# 08_DRIVER.net
KiCad netlist of a schematic drawn in Altium Designer
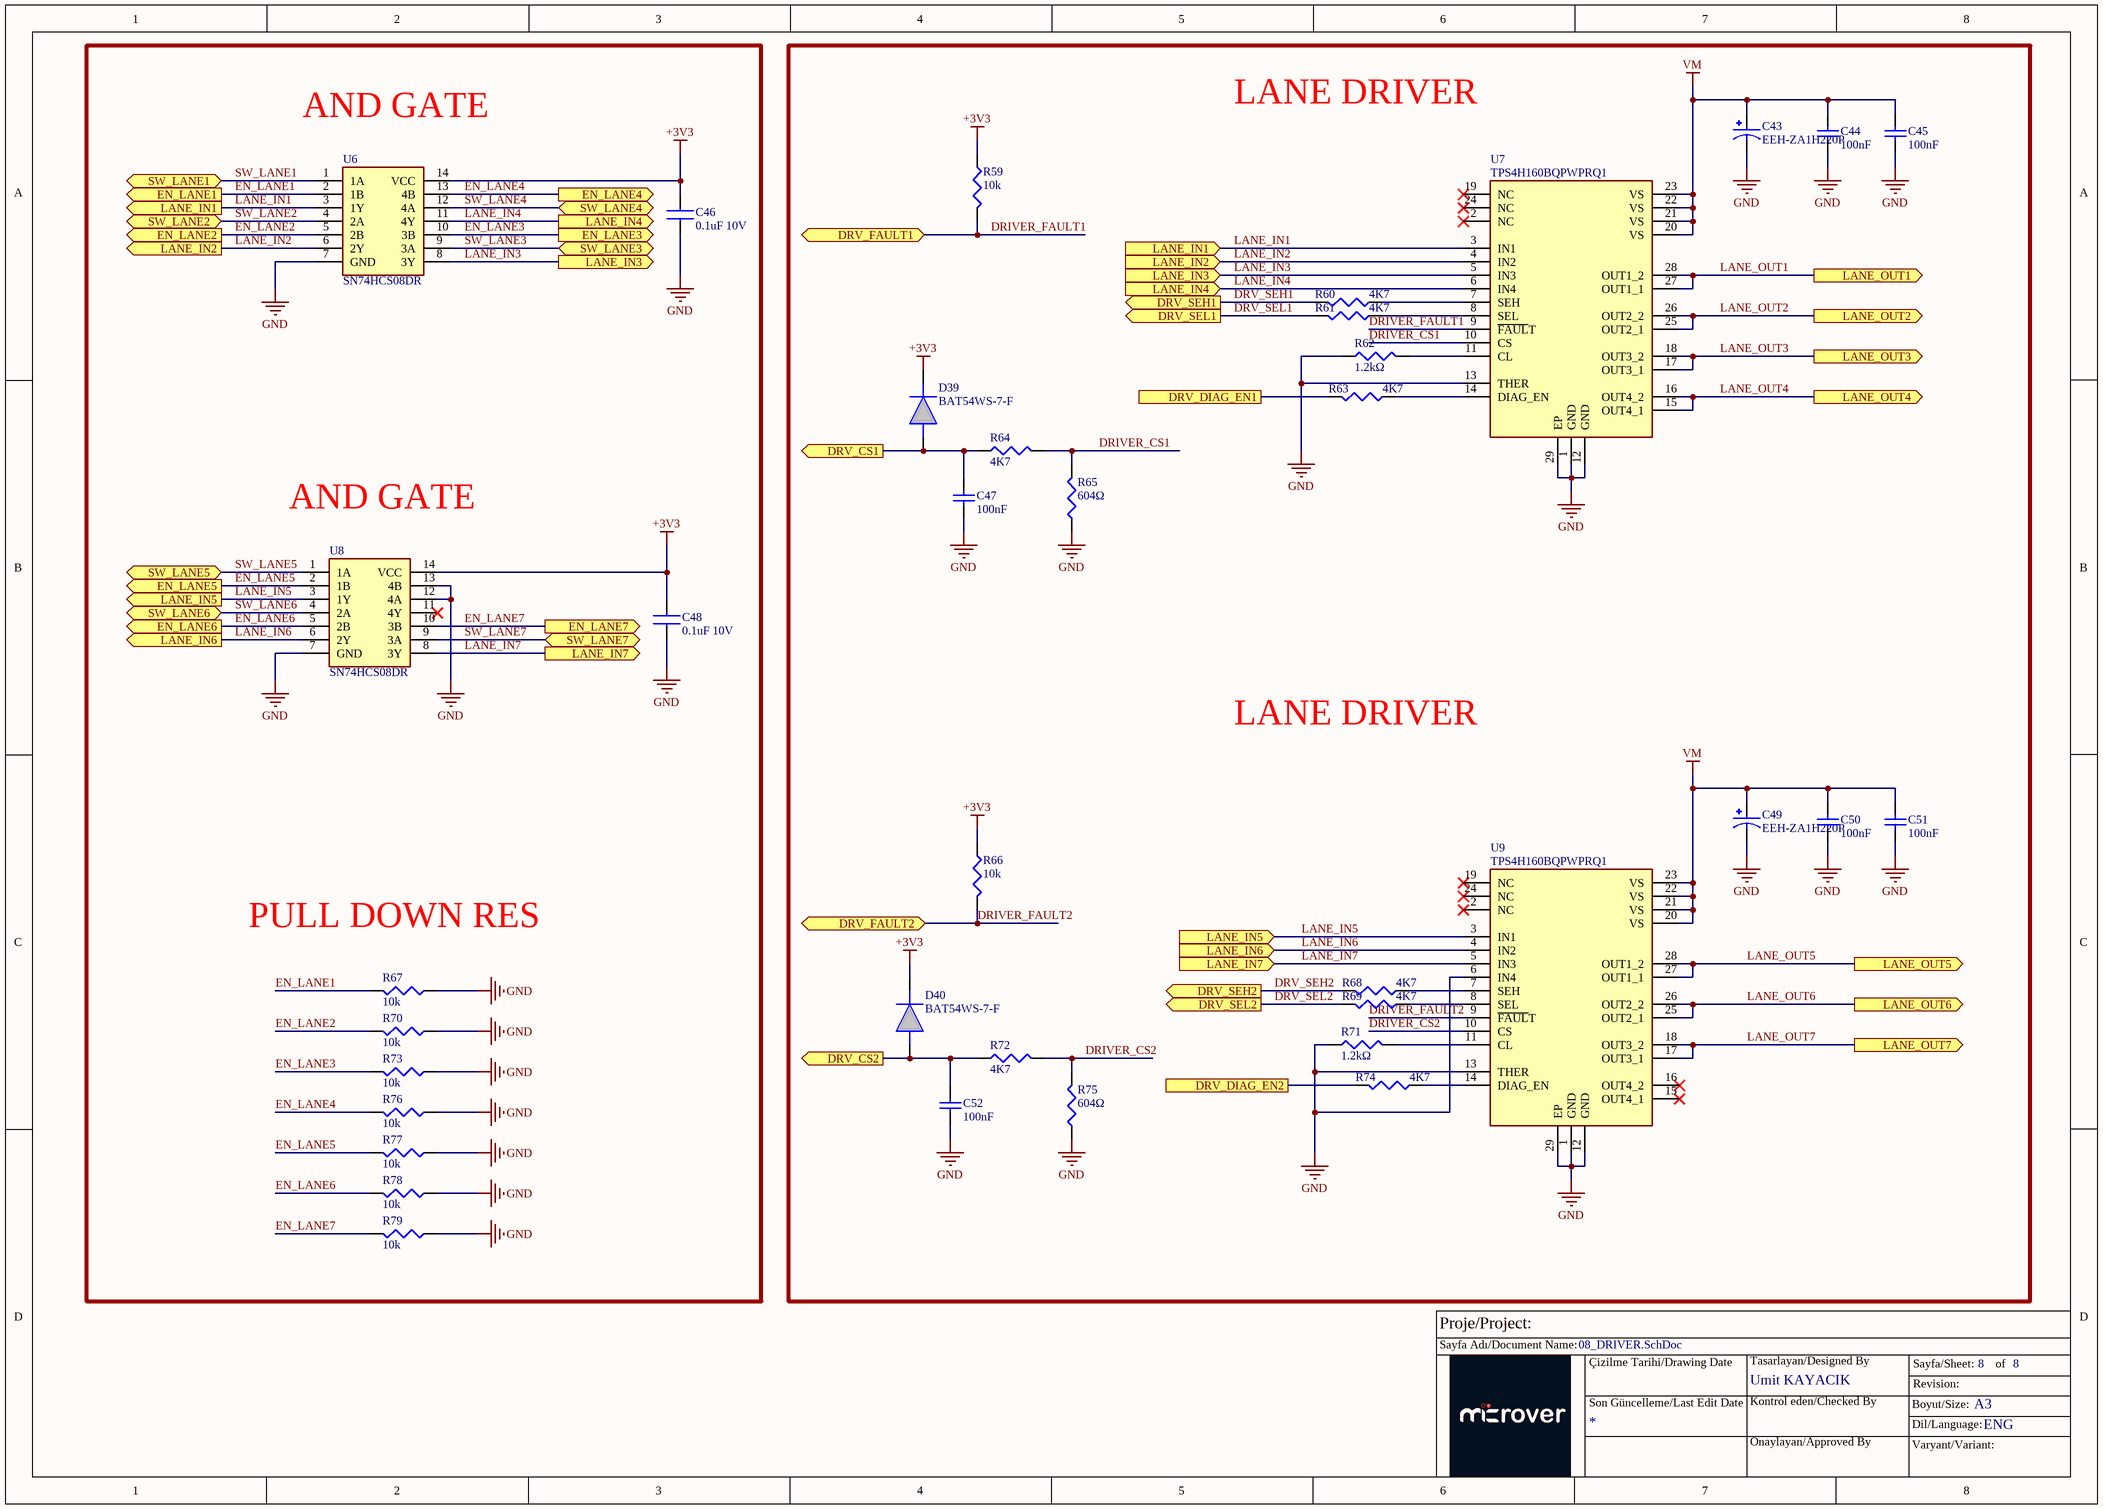
[diagram p0: 08_DRIVER.SchDoc]

(export (version "E")
  (design (tool "Eeschema 10.0.6"))
  (components
    (comp (ref "C43")
      (value "EEH-ZA1H220P")
      (footprint "CAP_EEHZA1H220P")
      (description "22 µF 50 V Aluminum - Polymer Capacitors Radial, Can - SMD 80mOhm 10000 Hrs @ 105°C")
      (fields (field (name "MANUFACTURER") "Panasonic Industry"))
      (libsource (lib "HW_ADHERENT_LANECTRL_R1") (part "EEH-ZA1H220P"))
    )
    (comp (ref "C44")
      (value "100nF")
      (footprint "CAP0603")
      (description "CAP CER 0.1UF 50V X7R 0603")
      (libsource (lib "HW_ADHERENT_LANECTRL_R1") (part "CAP0603_100nF_1"))
    )
    (comp (ref "C45")
      (value "100nF")
      (footprint "CAP0603")
      (description "CAP CER 0.1UF 50V X7R 0603")
      (libsource (lib "HW_ADHERENT_LANECTRL_R1") (part "CAP0603_100nF_1"))
    )
    (comp (ref "C46")
      (value "0.1uF 10V")
      (footprint "CAP0603")
      (description "0.1 µF ±10% 10V Ceramic Capacitor X7R 0603 (1608 Metric)")
      (fields
        (field (name "MANUFACTURER PART NUMBER") "0603ZC104KAT2A")
        (field (name "MOUSER PART NUMBER") "581-0603ZC104K")
      )
      (libsource (lib "HW_ADHERENT_LANECTRL_R1") (part "CAP0603_0.1uF_10V"))
    )
    (comp (ref "C47")
      (value "100nF")
      (footprint "CAP0603")
      (description "0.1 µF ±10% 50V Ceramic Capacitor X7R 0603 (1608 Metric)")
      (fields
        (field (name "MANUFACTURER PART NUMBER") "CL10B104KA8NNNC")
        (field (name "LCSC PART NUMBER") "C1590")
      )
      (libsource (lib "HW_ADHERENT_LANECTRL_R1") (part "CAP0603_100nF"))
    )
    (comp (ref "C48")
      (value "0.1uF 10V")
      (footprint "CAP0603")
      (description "0.1 µF ±10% 10V Ceramic Capacitor X7R 0603 (1608 Metric)")
      (fields
        (field (name "MANUFACTURER PART NUMBER") "0603ZC104KAT2A")
        (field (name "MOUSER PART NUMBER") "581-0603ZC104K")
      )
      (libsource (lib "HW_ADHERENT_LANECTRL_R1") (part "CAP0603_0.1uF_10V"))
    )
    (comp (ref "C49")
      (value "EEH-ZA1H220P")
      (footprint "CAP_EEHZA1H220P")
      (description "22 µF 50 V Aluminum - Polymer Capacitors Radial, Can - SMD 80mOhm 10000 Hrs @ 105°C")
      (fields (field (name "MANUFACTURER") "Panasonic Industry"))
      (libsource (lib "HW_ADHERENT_LANECTRL_R1") (part "EEH-ZA1H220P"))
    )
    (comp (ref "C50")
      (value "100nF")
      (footprint "CAP0603")
      (description "CAP CER 0.1UF 50V X7R 0603")
      (libsource (lib "HW_ADHERENT_LANECTRL_R1") (part "CAP0603_100nF_1"))
    )
    (comp (ref "C51")
      (value "100nF")
      (footprint "CAP0603")
      (description "CAP CER 0.1UF 50V X7R 0603")
      (libsource (lib "HW_ADHERENT_LANECTRL_R1") (part "CAP0603_100nF_1"))
    )
    (comp (ref "C52")
      (value "100nF")
      (footprint "CAP0603")
      (description "0.1 µF ±10% 50V Ceramic Capacitor X7R 0603 (1608 Metric)")
      (fields
        (field (name "MANUFACTURER PART NUMBER") "CL10B104KA8NNNC")
        (field (name "LCSC PART NUMBER") "C1590")
      )
      (libsource (lib "HW_ADHERENT_LANECTRL_R1") (part "CAP0603_100nF"))
    )
    (comp (ref "D39")
      (value "BAT54WS-7-F")
      (footprint "SOD2513X120N")
      (description "Diode 30 V 100mA Surface Mount SOD-323")
      (libsource (lib "HW_ADHERENT_LANECTRL_R1") (part "BAT54WS-7-F"))
    )
    (comp (ref "D40")
      (value "BAT54WS-7-F")
      (footprint "SOD2513X120N")
      (description "Diode 30 V 100mA Surface Mount SOD-323")
      (libsource (lib "HW_ADHERENT_LANECTRL_R1") (part "BAT54WS-7-F"))
    )
    (comp (ref "R59")
      (value "10k")
      (footprint "RES0603")
      (description "10 kOhms ±1% 0.125W, 1/8W Chip Resistor 0603 (1608 Metric) Anti-Sulfur Thin Film")
      (fields
        (field (name "MANUFACTURER PART NUMBER") "RNCP0603FTD10K0")
        (field (name "LCSC PART NUMBER") "C161803")
      )
      (libsource (lib "HW_ADHERENT_LANECTRL_R1") (part "RES0603_10K_%1_1"))
    )
    (comp (ref "R60")
      (value "4K7")
      (footprint "R 0603(1608)")
      (description "RES SMD 4.7K OHM 1% 1/10W 0603")
      (fields
        (field (name "MANUFACTURER") "Yageo")
        (field (name "MANUFACTURER PART NUMBER") "RC0603FR-074K7L")
      )
      (libsource (lib "HW_ADHERENT_LANECTRL_R1") (part "Res3_9_1"))
    )
    (comp (ref "R61")
      (value "4K7")
      (footprint "R 0603(1608)")
      (description "RES SMD 4.7K OHM 1% 1/10W 0603")
      (fields
        (field (name "MANUFACTURER") "Yageo")
        (field (name "MANUFACTURER PART NUMBER") "RC0603FR-074K7L")
      )
      (libsource (lib "HW_ADHERENT_LANECTRL_R1") (part "Res3_9_1"))
    )
    (comp (ref "R62")
      (value "1.2kΩ")
      (footprint "RES0603")
      (fields (field (name "JLCPCB PART#") "C22765"))
      (libsource (lib "HW_ADHERENT_LANECTRL_R1") (part "0603WAF1201T5E"))
    )
    (comp (ref "R63")
      (value "4K7")
      (footprint "R 0603(1608)")
      (description "RES SMD 4.7K OHM 1% 1/10W 0603")
      (fields
        (field (name "MANUFACTURER") "Yageo")
        (field (name "MANUFACTURER PART NUMBER") "RC0603FR-074K7L")
      )
      (libsource (lib "HW_ADHERENT_LANECTRL_R1") (part "Res3_9_1"))
    )
    (comp (ref "R64")
      (value "4K7")
      (footprint "R 0603(1608)")
      (description "RES SMD 4.7K OHM 1% 1/10W 0603")
      (fields
        (field (name "MANUFACTURER") "Yageo")
        (field (name "MANUFACTURER PART NUMBER") "RC0603FR-074K7L")
      )
      (libsource (lib "HW_ADHERENT_LANECTRL_R1") (part "Res3_9_1"))
    )
    (comp (ref "R65")
      (value "604Ω")
      (footprint "RES0603")
      (libsource (lib "HW_ADHERENT_LANECTRL_R1") (part "0603WAF6040T5E"))
    )
    (comp (ref "R66")
      (value "10k")
      (footprint "RES0603")
      (description "10 kOhms ±1% 0.125W, 1/8W Chip Resistor 0603 (1608 Metric) Anti-Sulfur Thin Film")
      (fields
        (field (name "MANUFACTURER PART NUMBER") "RNCP0603FTD10K0")
        (field (name "LCSC PART NUMBER") "C161803")
      )
      (libsource (lib "HW_ADHERENT_LANECTRL_R1") (part "RES0603_10K_%1_1"))
    )
    (comp (ref "R67")
      (value "10k")
      (footprint "RES0603")
      (description "10 kOhms ±1% 0.125W, 1/8W Chip Resistor 0603 (1608 Metric) Anti-Sulfur Thin Film")
      (fields
        (field (name "MANUFACTURER PART NUMBER") "RNCP0603FTD10K0")
        (field (name "LCSC PART NUMBER") "C161803")
      )
      (libsource (lib "HW_ADHERENT_LANECTRL_R1") (part "RES0603_10K_%1_1"))
    )
    (comp (ref "R68")
      (value "4K7")
      (footprint "R 0603(1608)")
      (description "RES SMD 4.7K OHM 1% 1/10W 0603")
      (fields
        (field (name "MANUFACTURER") "Yageo")
        (field (name "MANUFACTURER PART NUMBER") "RC0603FR-074K7L")
      )
      (libsource (lib "HW_ADHERENT_LANECTRL_R1") (part "Res3_9_1"))
    )
    (comp (ref "R69")
      (value "4K7")
      (footprint "R 0603(1608)")
      (description "RES SMD 4.7K OHM 1% 1/10W 0603")
      (fields
        (field (name "MANUFACTURER") "Yageo")
        (field (name "MANUFACTURER PART NUMBER") "RC0603FR-074K7L")
      )
      (libsource (lib "HW_ADHERENT_LANECTRL_R1") (part "Res3_9_1"))
    )
    (comp (ref "R70")
      (value "10k")
      (footprint "RES0603")
      (description "10 kOhms ±1% 0.125W, 1/8W Chip Resistor 0603 (1608 Metric) Anti-Sulfur Thin Film")
      (fields
        (field (name "MANUFACTURER PART NUMBER") "RNCP0603FTD10K0")
        (field (name "LCSC PART NUMBER") "C161803")
      )
      (libsource (lib "HW_ADHERENT_LANECTRL_R1") (part "RES0603_10K_%1_1"))
    )
    (comp (ref "R71")
      (value "1.2kΩ")
      (footprint "RES0603")
      (fields (field (name "JLCPCB PART#") "C22765"))
      (libsource (lib "HW_ADHERENT_LANECTRL_R1") (part "0603WAF1201T5E"))
    )
    (comp (ref "R72")
      (value "4K7")
      (footprint "R 0603(1608)")
      (description "RES SMD 4.7K OHM 1% 1/10W 0603")
      (fields
        (field (name "MANUFACTURER") "Yageo")
        (field (name "MANUFACTURER PART NUMBER") "RC0603FR-074K7L")
      )
      (libsource (lib "HW_ADHERENT_LANECTRL_R1") (part "Res3_9_1"))
    )
    (comp (ref "R73")
      (value "10k")
      (footprint "RES0603")
      (description "10 kOhms ±1% 0.125W, 1/8W Chip Resistor 0603 (1608 Metric) Anti-Sulfur Thin Film")
      (fields
        (field (name "MANUFACTURER PART NUMBER") "RNCP0603FTD10K0")
        (field (name "LCSC PART NUMBER") "C161803")
      )
      (libsource (lib "HW_ADHERENT_LANECTRL_R1") (part "RES0603_10K_%1_1"))
    )
    (comp (ref "R74")
      (value "4K7")
      (footprint "R 0603(1608)")
      (description "RES SMD 4.7K OHM 1% 1/10W 0603")
      (fields
        (field (name "MANUFACTURER") "Yageo")
        (field (name "MANUFACTURER PART NUMBER") "RC0603FR-074K7L")
      )
      (libsource (lib "HW_ADHERENT_LANECTRL_R1") (part "Res3_9_1"))
    )
    (comp (ref "R75")
      (value "604Ω")
      (footprint "RES0603")
      (libsource (lib "HW_ADHERENT_LANECTRL_R1") (part "0603WAF6040T5E"))
    )
    (comp (ref "R76")
      (value "10k")
      (footprint "RES0603")
      (description "10 kOhms ±1% 0.125W, 1/8W Chip Resistor 0603 (1608 Metric) Anti-Sulfur Thin Film")
      (fields
        (field (name "MANUFACTURER PART NUMBER") "RNCP0603FTD10K0")
        (field (name "LCSC PART NUMBER") "C161803")
      )
      (libsource (lib "HW_ADHERENT_LANECTRL_R1") (part "RES0603_10K_%1_1"))
    )
    (comp (ref "R77")
      (value "10k")
      (footprint "RES0603")
      (description "10 kOhms ±1% 0.125W, 1/8W Chip Resistor 0603 (1608 Metric) Anti-Sulfur Thin Film")
      (fields
        (field (name "MANUFACTURER PART NUMBER") "RNCP0603FTD10K0")
        (field (name "LCSC PART NUMBER") "C161803")
      )
      (libsource (lib "HW_ADHERENT_LANECTRL_R1") (part "RES0603_10K_%1_1"))
    )
    (comp (ref "R78")
      (value "10k")
      (footprint "RES0603")
      (description "10 kOhms ±1% 0.125W, 1/8W Chip Resistor 0603 (1608 Metric) Anti-Sulfur Thin Film")
      (fields
        (field (name "MANUFACTURER PART NUMBER") "RNCP0603FTD10K0")
        (field (name "LCSC PART NUMBER") "C161803")
      )
      (libsource (lib "HW_ADHERENT_LANECTRL_R1") (part "RES0603_10K_%1_1"))
    )
    (comp (ref "R79")
      (value "10k")
      (footprint "RES0603")
      (description "10 kOhms ±1% 0.125W, 1/8W Chip Resistor 0603 (1608 Metric) Anti-Sulfur Thin Film")
      (fields
        (field (name "MANUFACTURER PART NUMBER") "RNCP0603FTD10K0")
        (field (name "LCSC PART NUMBER") "C161803")
      )
      (libsource (lib "HW_ADHERENT_LANECTRL_R1") (part "RES0603_10K_%1_1"))
    )
    (comp (ref "U6")
      (value "SN74HCS08DR")
      (footprint "SOIC127P600X175-14N")
      (description "AND Gate IC 4 Channel Schmitt Trigger Input 14-SOIC")
      (libsource (lib "HW_ADHERENT_LANECTRL_R1") (part "SN74HCS08DR"))
    )
    (comp (ref "U7")
      (value "TPS4H160BQPWPRQ1")
      (footprint "SOP65P640X120-29N")
      (description "40-V, 160-mΩ, 4-ch automotive smart high-side switch with adjustable current limit")
      (fields (field (name "MPN") "TPS4H160-Q1"))
      (libsource (lib "HW_ADHERENT_LANECTRL_R1") (part "TPS4H160BQPWPRQ1"))
    )
    (comp (ref "U8")
      (value "SN74HCS08DR")
      (footprint "SOIC127P600X175-14N")
      (description "AND Gate IC 4 Channel Schmitt Trigger Input 14-SOIC")
      (libsource (lib "HW_ADHERENT_LANECTRL_R1") (part "SN74HCS08DR"))
    )
    (comp (ref "U9")
      (value "TPS4H160BQPWPRQ1")
      (footprint "SOP65P640X120-29N")
      (description "40-V, 160-mΩ, 4-ch automotive smart high-side switch with adjustable current limit")
      (fields (field (name "MPN") "TPS4H160-Q1"))
      (libsource (lib "HW_ADHERENT_LANECTRL_R1") (part "TPS4H160BQPWPRQ1"))
    )
  )
  (nets
    (net (code "1") (name "+3V3") (class "Default")
      (node (ref "C46") (pin "2") (pinfunction "2_2") (pintype "passive"))
      (node (ref "C48") (pin "2") (pinfunction "2_2") (pintype "passive"))
      (node (ref "D39") (pin "1") (pinfunction "K_1") (pintype "passive"))
      (node (ref "D40") (pin "1") (pinfunction "K_1") (pintype "passive"))
      (node (ref "R59") (pin "1") (pinfunction "1_1") (pintype "passive"))
      (node (ref "R66") (pin "1") (pinfunction "1_1") (pintype "passive"))
      (node (ref "U6") (pin "14") (pinfunction "VCC_14") (pintype "passive"))
      (node (ref "U8") (pin "14") (pinfunction "VCC_14") (pintype "passive"))
    )
    (net (code "2") (name "/DRIVER_CS1") (class "Default")
      (node (ref "R64") (pin "2") (pinfunction "2_2") (pintype "passive"))
      (node (ref "R65") (pin "2") (pinfunction "2_2") (pintype "passive"))
      (node (ref "U7") (pin "10") (pinfunction "CS_10") (pintype "passive"))
    )
    (net (code "3") (name "/DRIVER_CS2") (class "Default")
      (node (ref "R72") (pin "2") (pinfunction "2_2") (pintype "passive"))
      (node (ref "R75") (pin "2") (pinfunction "2_2") (pintype "passive"))
      (node (ref "U9") (pin "10") (pinfunction "CS_10") (pintype "passive"))
    )
    (net (code "4") (name "/DRIVER_FAULT1") (class "Default")
      (node (ref "R59") (pin "2") (pinfunction "2_2") (pintype "passive"))
      (node (ref "U7") (pin "9") (pinfunction "~{FAUL}T_9") (pintype "passive"))
    )
    (net (code "5") (name "/DRIVER_FAULT2") (class "Default")
      (node (ref "R66") (pin "2") (pinfunction "2_2") (pintype "passive"))
      (node (ref "U9") (pin "9") (pinfunction "~{FAUL}T_9") (pintype "passive"))
    )
    (net (code "6") (name "/DRV_CS1") (class "Default")
      (node (ref "C47") (pin "2") (pinfunction "2_2") (pintype "passive"))
      (node (ref "D39") (pin "2") (pinfunction "A_2") (pintype "passive"))
      (node (ref "R64") (pin "1") (pinfunction "1_1") (pintype "passive"))
    )
    (net (code "7") (name "/DRV_CS2") (class "Default")
      (node (ref "C52") (pin "2") (pinfunction "2_2") (pintype "passive"))
      (node (ref "D40") (pin "2") (pinfunction "A_2") (pintype "passive"))
      (node (ref "R72") (pin "1") (pinfunction "1_1") (pintype "passive"))
    )
    (net (code "8") (name "/DRV_DIAG_EN1") (class "Default")
      (node (ref "R63") (pin "2") (pinfunction "2_2") (pintype "passive"))
    )
    (net (code "9") (name "/DRV_DIAG_EN2") (class "Default")
      (node (ref "R74") (pin "2") (pinfunction "2_2") (pintype "passive"))
    )
    (net (code "10") (name "/DRV_SEH1") (class "Default")
      (node (ref "R60") (pin "2") (pinfunction "2_2") (pintype "passive"))
    )
    (net (code "11") (name "/DRV_SEH2") (class "Default")
      (node (ref "R68") (pin "2") (pinfunction "2_2") (pintype "passive"))
    )
    (net (code "12") (name "/DRV_SEL1") (class "Default")
      (node (ref "R61") (pin "2") (pinfunction "2_2") (pintype "passive"))
    )
    (net (code "13") (name "/DRV_SEL2") (class "Default")
      (node (ref "R69") (pin "2") (pinfunction "2_2") (pintype "passive"))
    )
    (net (code "14") (name "/EN_LANE1") (class "Default")
      (node (ref "R67") (pin "2") (pinfunction "2_2") (pintype "passive"))
      (node (ref "U6") (pin "2") (pinfunction "1B_2") (pintype "passive"))
    )
    (net (code "15") (name "/EN_LANE2") (class "Default")
      (node (ref "R70") (pin "2") (pinfunction "2_2") (pintype "passive"))
      (node (ref "U6") (pin "5") (pinfunction "2B_5") (pintype "passive"))
    )
    (net (code "16") (name "/EN_LANE3") (class "Default")
      (node (ref "R73") (pin "2") (pinfunction "2_2") (pintype "passive"))
      (node (ref "U6") (pin "10") (pinfunction "3B_10") (pintype "passive"))
    )
    (net (code "17") (name "/EN_LANE4") (class "Default")
      (node (ref "R76") (pin "2") (pinfunction "2_2") (pintype "passive"))
      (node (ref "U6") (pin "13") (pinfunction "4B_13") (pintype "passive"))
    )
    (net (code "18") (name "/EN_LANE5") (class "Default")
      (node (ref "R77") (pin "2") (pinfunction "2_2") (pintype "passive"))
      (node (ref "U8") (pin "2") (pinfunction "1B_2") (pintype "passive"))
    )
    (net (code "19") (name "/EN_LANE6") (class "Default")
      (node (ref "R78") (pin "2") (pinfunction "2_2") (pintype "passive"))
      (node (ref "U8") (pin "5") (pinfunction "2B_5") (pintype "passive"))
    )
    (net (code "20") (name "/EN_LANE7") (class "Default")
      (node (ref "R79") (pin "2") (pinfunction "2_2") (pintype "passive"))
      (node (ref "U8") (pin "10") (pinfunction "3B_10") (pintype "passive"))
    )
    (net (code "21") (name "/LANE_IN1") (class "Default")
      (node (ref "U6") (pin "3") (pinfunction "1Y_3") (pintype "passive"))
      (node (ref "U7") (pin "3") (pinfunction "IN1_3") (pintype "passive"))
    )
    (net (code "22") (name "/LANE_IN2") (class "Default")
      (node (ref "U6") (pin "6") (pinfunction "2Y_6") (pintype "passive"))
      (node (ref "U7") (pin "4") (pinfunction "IN2_4") (pintype "passive"))
    )
    (net (code "23") (name "/LANE_IN3") (class "Default")
      (node (ref "U6") (pin "8") (pinfunction "3Y_8") (pintype "passive"))
      (node (ref "U7") (pin "5") (pinfunction "IN3_5") (pintype "passive"))
    )
    (net (code "24") (name "/LANE_IN4") (class "Default")
      (node (ref "U6") (pin "11") (pinfunction "4Y_11") (pintype "passive"))
      (node (ref "U7") (pin "6") (pinfunction "IN4_6") (pintype "passive"))
    )
    (net (code "25") (name "/LANE_IN5") (class "Default")
      (node (ref "U8") (pin "3") (pinfunction "1Y_3") (pintype "passive"))
      (node (ref "U9") (pin "3") (pinfunction "IN1_3") (pintype "passive"))
    )
    (net (code "26") (name "/LANE_IN6") (class "Default")
      (node (ref "U8") (pin "6") (pinfunction "2Y_6") (pintype "passive"))
      (node (ref "U9") (pin "4") (pinfunction "IN2_4") (pintype "passive"))
    )
    (net (code "27") (name "/LANE_IN7") (class "Default")
      (node (ref "U8") (pin "8") (pinfunction "3Y_8") (pintype "passive"))
      (node (ref "U9") (pin "5") (pinfunction "IN3_5") (pintype "passive"))
    )
    (net (code "28") (name "/LANE_OUT1") (class "Default")
      (node (ref "U7") (pin "27") (pinfunction "OUT1_1_27") (pintype "passive"))
      (node (ref "U7") (pin "28") (pinfunction "OUT1_2_28") (pintype "passive"))
    )
    (net (code "29") (name "/LANE_OUT2") (class "Default")
      (node (ref "U7") (pin "25") (pinfunction "OUT2_1_25") (pintype "passive"))
      (node (ref "U7") (pin "26") (pinfunction "OUT2_2_26") (pintype "passive"))
    )
    (net (code "30") (name "/LANE_OUT3") (class "Default")
      (node (ref "U7") (pin "17") (pinfunction "OUT3_1_17") (pintype "passive"))
      (node (ref "U7") (pin "18") (pinfunction "OUT3_2_18") (pintype "passive"))
    )
    (net (code "31") (name "/LANE_OUT4") (class "Default")
      (node (ref "U7") (pin "15") (pinfunction "OUT4_1_15") (pintype "passive"))
      (node (ref "U7") (pin "16") (pinfunction "OUT4_2_16") (pintype "passive"))
    )
    (net (code "32") (name "/LANE_OUT5") (class "Default")
      (node (ref "U9") (pin "27") (pinfunction "OUT1_1_27") (pintype "passive"))
      (node (ref "U9") (pin "28") (pinfunction "OUT1_2_28") (pintype "passive"))
    )
    (net (code "33") (name "/LANE_OUT6") (class "Default")
      (node (ref "U9") (pin "25") (pinfunction "OUT2_1_25") (pintype "passive"))
      (node (ref "U9") (pin "26") (pinfunction "OUT2_2_26") (pintype "passive"))
    )
    (net (code "34") (name "/LANE_OUT7") (class "Default")
      (node (ref "U9") (pin "17") (pinfunction "OUT3_1_17") (pintype "passive"))
      (node (ref "U9") (pin "18") (pinfunction "OUT3_2_18") (pintype "passive"))
    )
    (net (code "35") (name "/SW_LANE1") (class "Default")
      (node (ref "U6") (pin "1") (pinfunction "1A_1") (pintype "passive"))
    )
    (net (code "36") (name "/SW_LANE2") (class "Default")
      (node (ref "U6") (pin "4") (pinfunction "2A_4") (pintype "passive"))
    )
    (net (code "37") (name "/SW_LANE3") (class "Default")
      (node (ref "U6") (pin "9") (pinfunction "3A_9") (pintype "passive"))
    )
    (net (code "38") (name "/SW_LANE4") (class "Default")
      (node (ref "U6") (pin "12") (pinfunction "4A_12") (pintype "passive"))
    )
    (net (code "39") (name "/SW_LANE5") (class "Default")
      (node (ref "U8") (pin "1") (pinfunction "1A_1") (pintype "passive"))
    )
    (net (code "40") (name "/SW_LANE6") (class "Default")
      (node (ref "U8") (pin "4") (pinfunction "2A_4") (pintype "passive"))
    )
    (net (code "41") (name "/SW_LANE7") (class "Default")
      (node (ref "U8") (pin "9") (pinfunction "3A_9") (pintype "passive"))
    )
    (net (code "42") (name "GND") (class "Default")
      (node (ref "C43") (pin "2") (pinfunction "2_2") (pintype "passive"))
      (node (ref "C44") (pin "1") (pinfunction "1_1") (pintype "passive"))
      (node (ref "C45") (pin "1") (pinfunction "1_1") (pintype "passive"))
      (node (ref "C46") (pin "1") (pinfunction "1_1") (pintype "passive"))
      (node (ref "C47") (pin "1") (pinfunction "1_1") (pintype "passive"))
      (node (ref "C48") (pin "1") (pinfunction "1_1") (pintype "passive"))
      (node (ref "C49") (pin "2") (pinfunction "2_2") (pintype "passive"))
      (node (ref "C50") (pin "1") (pinfunction "1_1") (pintype "passive"))
      (node (ref "C51") (pin "1") (pinfunction "1_1") (pintype "passive"))
      (node (ref "C52") (pin "1") (pinfunction "1_1") (pintype "passive"))
      (node (ref "R62") (pin "1") (pinfunction "1_1") (pintype "passive"))
      (node (ref "R65") (pin "1") (pinfunction "1_1") (pintype "passive"))
      (node (ref "R67") (pin "1") (pinfunction "1_1") (pintype "passive"))
      (node (ref "R70") (pin "1") (pinfunction "1_1") (pintype "passive"))
      (node (ref "R71") (pin "1") (pinfunction "1_1") (pintype "passive"))
      (node (ref "R73") (pin "1") (pinfunction "1_1") (pintype "passive"))
      (node (ref "R75") (pin "1") (pinfunction "1_1") (pintype "passive"))
      (node (ref "R76") (pin "1") (pinfunction "1_1") (pintype "passive"))
      (node (ref "R77") (pin "1") (pinfunction "1_1") (pintype "passive"))
      (node (ref "R78") (pin "1") (pinfunction "1_1") (pintype "passive"))
      (node (ref "R79") (pin "1") (pinfunction "1_1") (pintype "passive"))
      (node (ref "U6") (pin "7") (pinfunction "GND_7") (pintype "passive"))
      (node (ref "U7") (pin "1") (pinfunction "GND_1") (pintype "passive"))
      (node (ref "U7") (pin "12") (pinfunction "GND_12") (pintype "passive"))
      (node (ref "U7") (pin "13") (pinfunction "THER_13") (pintype "passive"))
      (node (ref "U7") (pin "29") (pinfunction "EP_29") (pintype "passive"))
      (node (ref "U8") (pin "12") (pinfunction "4A_12") (pintype "passive"))
      (node (ref "U8") (pin "13") (pinfunction "4B_13") (pintype "passive"))
      (node (ref "U8") (pin "7") (pinfunction "GND_7") (pintype "passive"))
      (node (ref "U9") (pin "1") (pinfunction "GND_1") (pintype "passive"))
      (node (ref "U9") (pin "12") (pinfunction "GND_12") (pintype "passive"))
      (node (ref "U9") (pin "13") (pinfunction "THER_13") (pintype "passive"))
      (node (ref "U9") (pin "29") (pinfunction "EP_29") (pintype "passive"))
      (node (ref "U9") (pin "6") (pinfunction "IN4_6") (pintype "passive"))
    )
    (net (code "43") (name "Net-(U7-CL)") (class "Default")
      (node (ref "R62") (pin "2") (pinfunction "2_2") (pintype "passive"))
      (node (ref "U7") (pin "11") (pinfunction "CL_11") (pintype "passive"))
    )
    (net (code "44") (name "Net-(U7-DIAG_EN)") (class "Default")
      (node (ref "R63") (pin "1") (pinfunction "1_1") (pintype "passive"))
      (node (ref "U7") (pin "14") (pinfunction "DIAG_EN_14") (pintype "passive"))
    )
    (net (code "45") (name "Net-(U7-SEH)") (class "Default")
      (node (ref "R60") (pin "1") (pinfunction "1_1") (pintype "passive"))
      (node (ref "U7") (pin "7") (pinfunction "SEH_7") (pintype "passive"))
    )
    (net (code "46") (name "Net-(U7-SEL)") (class "Default")
      (node (ref "R61") (pin "1") (pinfunction "1_1") (pintype "passive"))
      (node (ref "U7") (pin "8") (pinfunction "SEL_8") (pintype "passive"))
    )
    (net (code "47") (name "Net-(U9-CL)") (class "Default")
      (node (ref "R71") (pin "2") (pinfunction "2_2") (pintype "passive"))
      (node (ref "U9") (pin "11") (pinfunction "CL_11") (pintype "passive"))
    )
    (net (code "48") (name "Net-(U9-DIAG_EN)") (class "Default")
      (node (ref "R74") (pin "1") (pinfunction "1_1") (pintype "passive"))
      (node (ref "U9") (pin "14") (pinfunction "DIAG_EN_14") (pintype "passive"))
    )
    (net (code "49") (name "Net-(U9-SEH)") (class "Default")
      (node (ref "R68") (pin "1") (pinfunction "1_1") (pintype "passive"))
      (node (ref "U9") (pin "7") (pinfunction "SEH_7") (pintype "passive"))
    )
    (net (code "50") (name "Net-(U9-SEL)") (class "Default")
      (node (ref "R69") (pin "1") (pinfunction "1_1") (pintype "passive"))
      (node (ref "U9") (pin "8") (pinfunction "SEL_8") (pintype "passive"))
    )
    (net (code "51") (name "VM") (class "Default")
      (node (ref "C43") (pin "1") (pinfunction "1_1") (pintype "passive"))
      (node (ref "C44") (pin "2") (pinfunction "2_2") (pintype "passive"))
      (node (ref "C45") (pin "2") (pinfunction "2_2") (pintype "passive"))
      (node (ref "C49") (pin "1") (pinfunction "1_1") (pintype "passive"))
      (node (ref "C50") (pin "2") (pinfunction "2_2") (pintype "passive"))
      (node (ref "C51") (pin "2") (pinfunction "2_2") (pintype "passive"))
      (node (ref "U7") (pin "20") (pinfunction "VS_20") (pintype "passive"))
      (node (ref "U7") (pin "21") (pinfunction "VS_21") (pintype "passive"))
      (node (ref "U7") (pin "22") (pinfunction "VS_22") (pintype "passive"))
      (node (ref "U7") (pin "23") (pinfunction "VS_23") (pintype "passive"))
      (node (ref "U9") (pin "20") (pinfunction "VS_20") (pintype "passive"))
      (node (ref "U9") (pin "21") (pinfunction "VS_21") (pintype "passive"))
      (node (ref "U9") (pin "22") (pinfunction "VS_22") (pintype "passive"))
      (node (ref "U9") (pin "23") (pinfunction "VS_23") (pintype "passive"))
    )
    (net (code "52") (name "unconnected-(U7-NC-Pad2)") (class "Default")
      (node (ref "U7") (pin "2") (pinfunction "NC_2") (pintype "passive+no_connect"))
    )
    (net (code "53") (name "unconnected-(U7-NC-Pad19)") (class "Default")
      (node (ref "U7") (pin "19") (pinfunction "NC_19") (pintype "passive+no_connect"))
    )
    (net (code "54") (name "unconnected-(U7-NC-Pad24)") (class "Default")
      (node (ref "U7") (pin "24") (pinfunction "NC_24") (pintype "passive+no_connect"))
    )
    (net (code "55") (name "unconnected-(U8-4Y-Pad11)") (class "Default")
      (node (ref "U8") (pin "11") (pinfunction "4Y_11") (pintype "passive+no_connect"))
    )
    (net (code "56") (name "unconnected-(U9-NC-Pad2)") (class "Default")
      (node (ref "U9") (pin "2") (pinfunction "NC_2") (pintype "passive+no_connect"))
    )
    (net (code "57") (name "unconnected-(U9-NC-Pad19)") (class "Default")
      (node (ref "U9") (pin "19") (pinfunction "NC_19") (pintype "passive+no_connect"))
    )
    (net (code "58") (name "unconnected-(U9-NC-Pad24)") (class "Default")
      (node (ref "U9") (pin "24") (pinfunction "NC_24") (pintype "passive+no_connect"))
    )
    (net (code "59") (name "unconnected-(U9-OUT4_1-Pad15)") (class "Default")
      (node (ref "U9") (pin "15") (pinfunction "OUT4_1_15") (pintype "passive+no_connect"))
    )
    (net (code "60") (name "unconnected-(U9-OUT4_2-Pad16)") (class "Default")
      (node (ref "U9") (pin "16") (pinfunction "OUT4_2_16") (pintype "passive+no_connect"))
    )
  )
)
